# CAN.net
KiCad netlist of a schematic drawn in Altium Designer
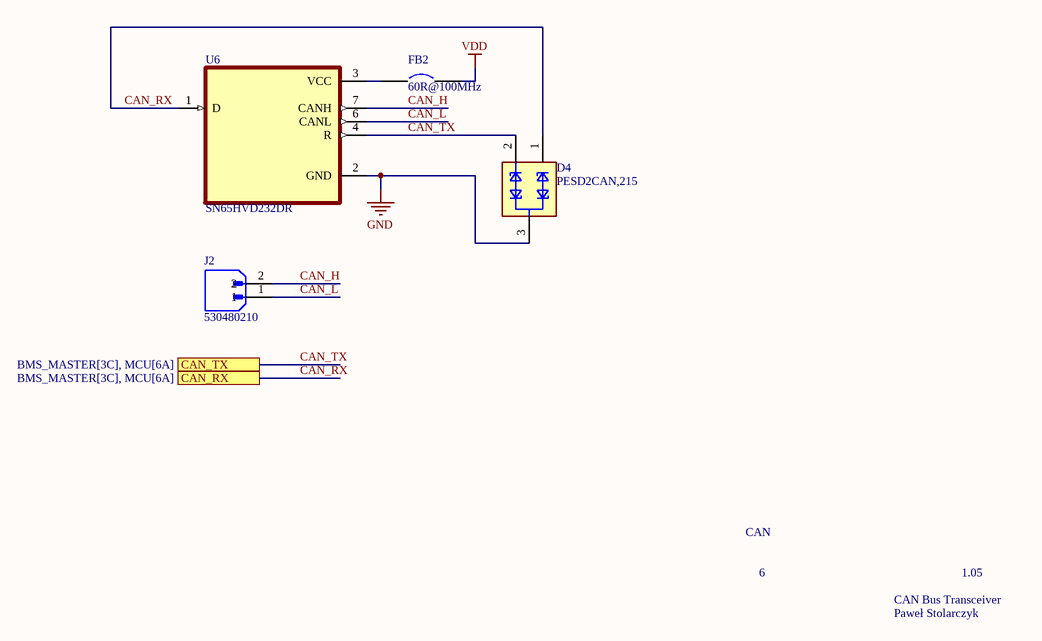
[diagram p0: CAN.SchDoc]

(export (version "E")
  (design (tool "Eeschema 10.0.6"))
  (components
    (comp (ref "D4")
      (value "PESD2CAN,215")
      (footprint "SOT95P230X110-3N")
      (description "ESD Suppressor Diode TVS Bi-Dir 24V Automotive 3-Pin SOT-23 T/R")
      (fields (field (name "MF") "Nexperia USA Inc."))
      (libsource (lib "PESD2CAN_215") (part "PESD2CAN,215"))
    )
    (comp (ref "FB2")
      (value "60R@100MHz")
      (footprint "0402")
      (description "Circuit Breaker")
      (fields (field (name "PUBLISHER") "Altium Limited"))
      (libsource (lib "Miscellaneous Devices") (part "Circuit Breaker"))
    )
    (comp (ref "J2")
      (value "530480210")
      (footprint "MOLEX_530480210")
      (description "Conn Shrouded Header (4 Sides) HDR 2 POS 1.25mm Solder RA Side Entry Thru-Hole PicoBladeâ„¢ Tray")
      (fields (field (name "MF") "Molex"))
      (libsource (lib "530480210") (part "530480210"))
    )
    (comp (ref "U6")
      (value "SN65HVD232DR")
      (footprint "SOIC127P599X175-8N")
      (description "3.3 V CAN Transceiver 8-SOIC -40 to 85")
      (fields (field (name "MF") "Texas Instruments"))
      (libsource (lib "SN65HVD232DR") (part "SN65HVD232DR"))
    )
  )
  (nets
    (net (code "1") (name "/CAN_H") (class "Default")
      (node (ref "J2") (pin "2") (pinfunction "2_2") (pintype "passive"))
      (node (ref "U6") (pin "7") (pinfunction "CANH_7") (pintype "output"))
    )
    (net (code "2") (name "/CAN_L") (class "Default")
      (node (ref "J2") (pin "1") (pinfunction "1_1") (pintype "passive"))
      (node (ref "U6") (pin "6") (pinfunction "CANL_6") (pintype "output"))
    )
    (net (code "3") (name "/CAN_RX") (class "Default")
      (node (ref "D4") (pin "1") (pinfunction "1_1") (pintype "passive"))
      (node (ref "U6") (pin "1") (pinfunction "D_1") (pintype "input"))
    )
    (net (code "4") (name "/CAN_TX") (class "Default")
      (node (ref "D4") (pin "2") (pinfunction "2_2") (pintype "passive"))
      (node (ref "U6") (pin "4") (pinfunction "R_4") (pintype "output"))
    )
    (net (code "5") (name "GND") (class "Default")
      (node (ref "D4") (pin "3") (pinfunction "3_3") (pintype "passive"))
      (node (ref "U6") (pin "2") (pinfunction "GND_2") (pintype "power_in"))
    )
    (net (code "6") (name "Net-(U6-VCC)") (class "Default")
      (node (ref "FB2") (pin "1") (pinfunction "1_1") (pintype "passive"))
      (node (ref "U6") (pin "3") (pinfunction "VCC_3") (pintype "power_in"))
    )
    (net (code "7") (name "VDD") (class "Default")
      (node (ref "FB2") (pin "2") (pinfunction "2_2") (pintype "passive"))
    )
  )
)
